# 02-USER_IO.net
KiCad netlist of a schematic drawn in Altium Designer
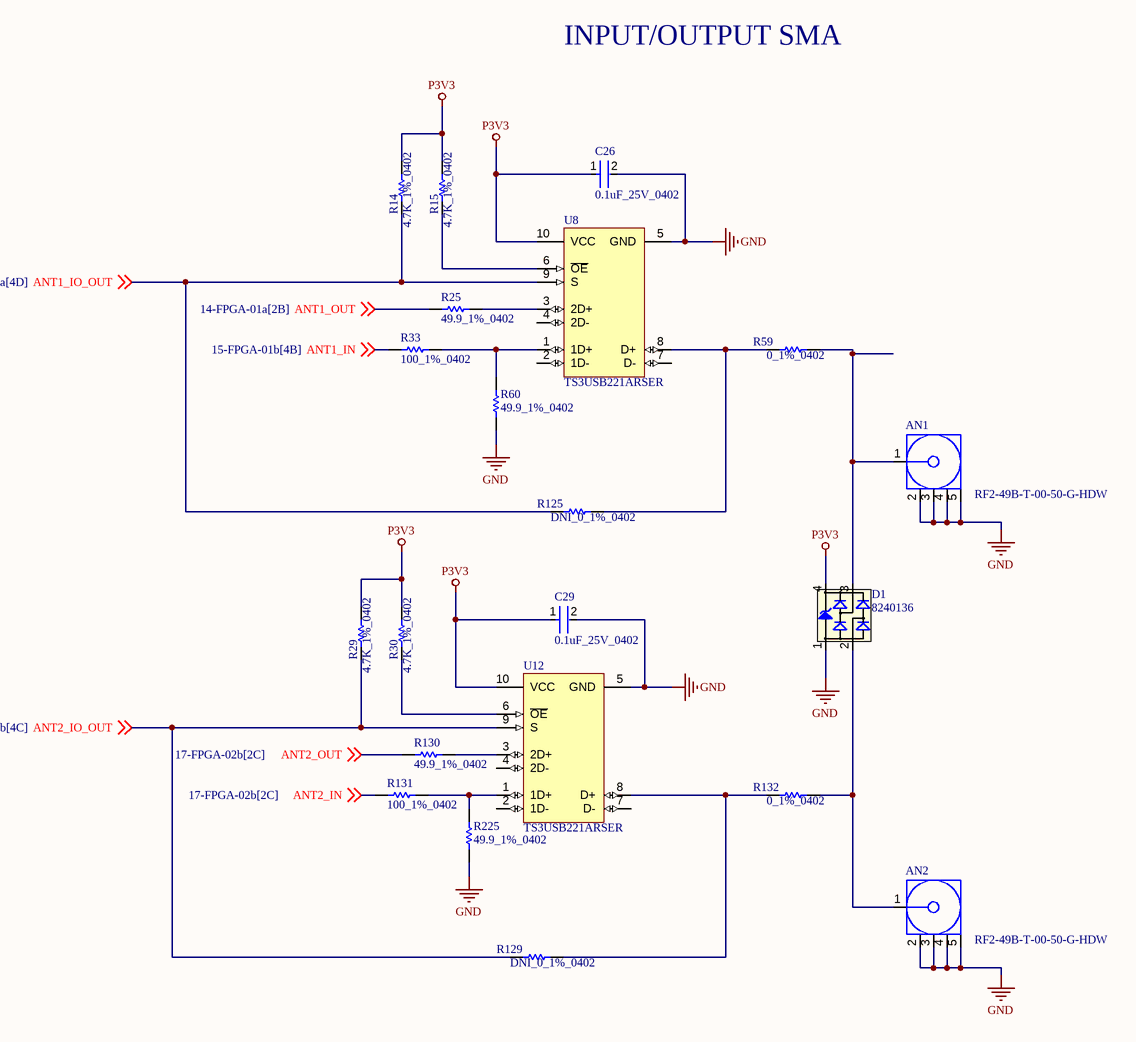
[diagram p0: 02-USER_IO.SchDoc]

(export (version "E")
  (design (tool "Eeschema 10.0.6"))
  (components
    (comp (ref "AN1")
      (value "RF2-49B-T-00-50-G-HDW")
      (footprint "AMPH-901-143-6RFX_V")
      (description "Coaxial connector, 50 Ohm, -65 to 165 degC, 5-Pin THD, RoHS, Bulk")
      (fields (field (name "MANUFACTURER") "Amphenol"))
      (libsource (lib "Altium Content Vault") (part "CN-S-4F-RF5"))
    )
    (comp (ref "AN2")
      (value "RF2-49B-T-00-50-G-HDW")
      (footprint "AMPH-901-143-6RFX_V")
      (description "Coaxial connector, 50 Ohm, -65 to 165 degC, 5-Pin THD, RoHS, Bulk")
      (fields (field (name "MANUFACTURER") "Amphenol"))
      (libsource (lib "Altium Content Vault") (part "CN-S-4F-RF5"))
    )
    (comp (ref "C26")
      (value "0.1uF_25V_0402")
      (footprint "FP-0402-L_1_0_1-W_0_5_0_1-IPC_C")
      (description "General Purpose Ceramic Capacitor, 0402, 100nF, 10%, X7R, 15%, 25V")
      (fields (field (name "VOLTAGE") "25V") (field (name "TOLERANCE") "10%"))
      (libsource (lib "Altium Content Vault") (part "b4654b650e69147ec39a6b967a45e02"))
    )
    (comp (ref "C29")
      (value "0.1uF_25V_0402")
      (footprint "FP-0402-L_1_0_1-W_0_5_0_1-IPC_C")
      (description "General Purpose Ceramic Capacitor, 0402, 100nF, 10%, X7R, 15%, 25V")
      (fields (field (name "VOLTAGE") "25V") (field (name "TOLERANCE") "10%"))
      (libsource (lib "Altium Content Vault") (part "b4654b650e69147ec39a6b967a45e02"))
    )
    (comp (ref "D1")
      (value "8240136")
      (footprint "SOT143-4L")
      (description "TVS Diode WE-TVS-HS, VRWM=3.3V")
      (fields (field (name "MANUFACTURER") "Wuerth Elektronik"))
      (libsource (lib "Altium Content Vault") (part "WE-TVS-HS-4"))
    )
    (comp (ref "R14")
      (value "4.7K_1%_0402")
      (footprint "RESC1005X40X25NL10T10")
      (fields (field (name "MANUFACTURER") "Bourns") (field (name "PART NUMBER") "CR0402-FX-4701GLF"))
      (libsource (lib "Altium Content Vault") (part "RES"))
    )
    (comp (ref "R15")
      (value "4.7K_1%_0402")
      (footprint "RESC1005X40X25NL10T10")
      (fields (field (name "MANUFACTURER") "Bourns") (field (name "PART NUMBER") "CR0402-FX-4701GLF"))
      (libsource (lib "Altium Content Vault") (part "RES"))
    )
    (comp (ref "R25")
      (value "49.9_1%_0402")
      (footprint "RESC1005X40X25NL10T10")
      (fields (field (name "PART NUMBER") "RK73H1ETTP49R9F") (field (name "MANUFACTURER") "KOA Speer"))
      (libsource (lib "Altium Content Vault") (part "RES"))
    )
    (comp (ref "R29")
      (value "4.7K_1%_0402")
      (footprint "RESC1005X40X25NL10T10")
      (fields (field (name "MANUFACTURER") "Bourns") (field (name "PART NUMBER") "CR0402-FX-4701GLF"))
      (libsource (lib "Altium Content Vault") (part "RES"))
    )
    (comp (ref "R30")
      (value "4.7K_1%_0402")
      (footprint "RESC1005X40X25NL10T10")
      (fields (field (name "MANUFACTURER") "Bourns") (field (name "PART NUMBER") "CR0402-FX-4701GLF"))
      (libsource (lib "Altium Content Vault") (part "RES"))
    )
    (comp (ref "R33")
      (value "100_1%_0402")
      (footprint "RESC1005X40X25NL05T10")
      (fields (field (name "MANUFACTURER") "Yageo") (field (name "PART NUMBER") "RC0402FR-13100RL"))
      (libsource (lib "Altium Content Vault") (part "RES"))
    )
    (comp (ref "R59")
      (value "0_1%_0402")
      (footprint "RESC1005X40X25LL05T05")
      (description "Chip Resistor, 0 Ohm, 0.1 W, -55 to 155 degC, 0402 (1005 Metric), RoHS, Tape and Reel")
      (fields (field (name "MANUFACTURER") "Panasonic") (field (name "TOLERANCE") "5%"))
      (libsource (lib "Altium Content Vault") (part "RES-2"))
    )
    (comp (ref "R60")
      (value "49.9_1%_0402")
      (footprint "RESC1005X40X25NL10T10")
      (fields (field (name "PART NUMBER") "RK73H1ETTP49R9F") (field (name "MANUFACTURER") "KOA Speer"))
      (libsource (lib "Altium Content Vault") (part "RES"))
    )
    (comp (ref "R125")
      (value "DNI_0_1%_0402")
      (footprint "RESC1005X40X25LL05T05")
      (description "Chip Resistor, 0 Ohm, 0.1 W, -55 to 155 degC, 0402 (1005 Metric), RoHS, Tape and Reel")
      (fields (field (name "MANUFACTURER") "Panasonic") (field (name "TOLERANCE") "5%"))
      (libsource (lib "Altium Content Vault") (part "RES-2"))
    )
    (comp (ref "R129")
      (value "DNI_0_1%_0402")
      (footprint "RESC1005X40X25LL05T05")
      (description "Chip Resistor, 0 Ohm, 0.1 W, -55 to 155 degC, 0402 (1005 Metric), RoHS, Tape and Reel")
      (fields (field (name "MANUFACTURER") "Panasonic") (field (name "TOLERANCE") "5%"))
      (libsource (lib "Altium Content Vault") (part "RES-2"))
    )
    (comp (ref "R130")
      (value "49.9_1%_0402")
      (footprint "RESC1005X40X25NL10T10")
      (fields (field (name "PART NUMBER") "RK73H1ETTP49R9F") (field (name "MANUFACTURER") "KOA Speer"))
      (libsource (lib "Altium Content Vault") (part "RES"))
    )
    (comp (ref "R131")
      (value "100_1%_0402")
      (footprint "RESC1005X40X25NL05T10")
      (fields (field (name "MANUFACTURER") "Yageo") (field (name "PART NUMBER") "RC0402FR-13100RL"))
      (libsource (lib "Altium Content Vault") (part "RES"))
    )
    (comp (ref "R132")
      (value "0_1%_0402")
      (footprint "RESC1005X40X25LL05T05")
      (description "Chip Resistor, 0 Ohm, 0.1 W, -55 to 155 degC, 0402 (1005 Metric), RoHS, Tape and Reel")
      (fields (field (name "MANUFACTURER") "Panasonic") (field (name "TOLERANCE") "5%"))
      (libsource (lib "Altium Content Vault") (part "RES-2"))
    )
    (comp (ref "R225")
      (value "49.9_1%_0402")
      (footprint "RESC1005X40X25NL10T10")
      (fields (field (name "PART NUMBER") "RK73H1ETTP49R9F") (field (name "MANUFACTURER") "KOA Speer"))
      (libsource (lib "Altium Content Vault") (part "RES"))
    )
    (comp (ref "U8")
      (value "TS3USB221ARSER")
      (footprint "RSE0010A_V")
      (fields (field (name "MANUFACTURER") "Texas Instruments"))
      (libsource (lib "Altium Content Vault") (part "TI-TS3USB221A-UQFN_RSE-10"))
    )
    (comp (ref "U12")
      (value "TS3USB221ARSER")
      (footprint "RSE0010A_V")
      (fields (field (name "MANUFACTURER") "Texas Instruments"))
      (libsource (lib "Altium Content Vault") (part "TI-TS3USB221A-UQFN_RSE-10"))
    )
  )
  (nets
    (net (code "1") (name "ANT1_IN") (class "Default")
      (node (ref "R33") (pin "1") (pinfunction "1_1") (pintype "passive"))
    )
    (net (code "2") (name "ANT1_IO_OUT") (class "Default")
      (node (ref "R125") (pin "1") (pinfunction "1_1") (pintype "passive"))
      (node (ref "R14") (pin "2") (pinfunction "2_2") (pintype "passive"))
      (node (ref "U8") (pin "9") (pinfunction "S_9") (pintype "input"))
    )
    (net (code "3") (name "ANT1_OUT") (class "Default")
      (node (ref "R25") (pin "1") (pinfunction "1_1") (pintype "passive"))
    )
    (net (code "4") (name "ANT2_IN") (class "Default")
      (node (ref "R131") (pin "1") (pinfunction "1_1") (pintype "passive"))
    )
    (net (code "5") (name "ANT2_IO_OUT") (class "Default")
      (node (ref "R129") (pin "1") (pinfunction "1_1") (pintype "passive"))
      (node (ref "R29") (pin "2") (pinfunction "2_2") (pintype "passive"))
      (node (ref "U12") (pin "9") (pinfunction "S_9") (pintype "input"))
    )
    (net (code "6") (name "ANT2_OUT") (class "Default")
      (node (ref "R130") (pin "1") (pinfunction "1_1") (pintype "passive"))
    )
    (net (code "7") (name "GND") (class "Default")
      (node (ref "AN1") (pin "2") (pinfunction "2_2") (pintype "passive"))
      (node (ref "AN1") (pin "3") (pinfunction "3_3") (pintype "passive"))
      (node (ref "AN1") (pin "4") (pinfunction "4_4") (pintype "passive"))
      (node (ref "AN1") (pin "5") (pinfunction "5_5") (pintype "passive"))
      (node (ref "AN2") (pin "2") (pinfunction "2_2") (pintype "passive"))
      (node (ref "AN2") (pin "3") (pinfunction "3_3") (pintype "passive"))
      (node (ref "AN2") (pin "4") (pinfunction "4_4") (pintype "passive"))
      (node (ref "AN2") (pin "5") (pinfunction "5_5") (pintype "passive"))
      (node (ref "C26") (pin "2") (pinfunction "2_2") (pintype "passive"))
      (node (ref "C29") (pin "2") (pinfunction "2_2") (pintype "passive"))
      (node (ref "D1") (pin "1") (pinfunction "GND_1") (pintype "passive"))
      (node (ref "R225") (pin "1") (pinfunction "1_1") (pintype "passive"))
      (node (ref "R60") (pin "1") (pinfunction "1_1") (pintype "passive"))
      (node (ref "U12") (pin "5") (pinfunction "GND_5") (pintype "power_in"))
      (node (ref "U8") (pin "5") (pinfunction "GND_5") (pintype "power_in"))
    )
    (net (code "8") (name "Net-(D1-I{slash}O1)") (class "Default")
      (node (ref "AN2") (pin "1") (pinfunction "1_1") (pintype "passive"))
      (node (ref "D1") (pin "2") (pinfunction "I/O1_2") (pintype "passive"))
      (node (ref "R132") (pin "2") (pinfunction "2_2") (pintype "passive"))
    )
    (net (code "9") (name "Net-(D1-I{slash}O2)") (class "Default")
      (node (ref "AN1") (pin "1") (pinfunction "1_1") (pintype "passive"))
      (node (ref "D1") (pin "3") (pinfunction "I/O2_3") (pintype "passive"))
      (node (ref "R59") (pin "2") (pinfunction "2_2") (pintype "passive"))
    )
    (net (code "10") (name "Net-(U8-1D+)") (class "Default")
      (node (ref "R33") (pin "2") (pinfunction "2_2") (pintype "passive"))
      (node (ref "R60") (pin "2") (pinfunction "2_2") (pintype "passive"))
      (node (ref "U8") (pin "1") (pinfunction "1D+_1") (pintype "bidirectional"))
    )
    (net (code "11") (name "Net-(U8-2D+)") (class "Default")
      (node (ref "R25") (pin "2") (pinfunction "2_2") (pintype "passive"))
      (node (ref "U8") (pin "3") (pinfunction "2D+_3") (pintype "bidirectional"))
    )
    (net (code "12") (name "Net-(U8-D+)") (class "Default")
      (node (ref "R125") (pin "2") (pinfunction "2_2") (pintype "passive"))
      (node (ref "R59") (pin "1") (pinfunction "1_1") (pintype "passive"))
      (node (ref "U8") (pin "8") (pinfunction "D+_8") (pintype "bidirectional"))
    )
    (net (code "13") (name "Net-(U8-~{OE})") (class "Default")
      (node (ref "R15") (pin "2") (pinfunction "2_2") (pintype "passive"))
      (node (ref "U8") (pin "6") (pinfunction "~{OE}_6") (pintype "input"))
    )
    (net (code "14") (name "Net-(U12-1D+)") (class "Default")
      (node (ref "R131") (pin "2") (pinfunction "2_2") (pintype "passive"))
      (node (ref "R225") (pin "2") (pinfunction "2_2") (pintype "passive"))
      (node (ref "U12") (pin "1") (pinfunction "1D+_1") (pintype "bidirectional"))
    )
    (net (code "15") (name "Net-(U12-2D+)") (class "Default")
      (node (ref "R130") (pin "2") (pinfunction "2_2") (pintype "passive"))
      (node (ref "U12") (pin "3") (pinfunction "2D+_3") (pintype "bidirectional"))
    )
    (net (code "16") (name "Net-(U12-D+)") (class "Default")
      (node (ref "R129") (pin "2") (pinfunction "2_2") (pintype "passive"))
      (node (ref "R132") (pin "1") (pinfunction "1_1") (pintype "passive"))
      (node (ref "U12") (pin "8") (pinfunction "D+_8") (pintype "bidirectional"))
    )
    (net (code "17") (name "Net-(U12-~{OE})") (class "Default")
      (node (ref "R30") (pin "2") (pinfunction "2_2") (pintype "passive"))
      (node (ref "U12") (pin "6") (pinfunction "~{OE}_6") (pintype "input"))
    )
    (net (code "18") (name "P3V3") (class "Default")
      (node (ref "C26") (pin "1") (pinfunction "1_1") (pintype "passive"))
      (node (ref "C29") (pin "1") (pinfunction "1_1") (pintype "passive"))
      (node (ref "D1") (pin "4") (pinfunction "VDD_4") (pintype "passive"))
      (node (ref "R14") (pin "1") (pinfunction "1_1") (pintype "passive"))
      (node (ref "R15") (pin "1") (pinfunction "1_1") (pintype "passive"))
      (node (ref "R29") (pin "1") (pinfunction "1_1") (pintype "passive"))
      (node (ref "R30") (pin "1") (pinfunction "1_1") (pintype "passive"))
      (node (ref "U12") (pin "10") (pinfunction "VCC_10") (pintype "power_in"))
      (node (ref "U8") (pin "10") (pinfunction "VCC_10") (pintype "power_in"))
    )
    (net (code "19") (name "unconnected-(U8-1D--Pad2)") (class "Default")
      (node (ref "U8") (pin "2") (pinfunction "1D-_2") (pintype "bidirectional"))
    )
    (net (code "20") (name "unconnected-(U8-2D--Pad4)") (class "Default")
      (node (ref "U8") (pin "4") (pinfunction "2D-_4") (pintype "bidirectional"))
    )
    (net (code "21") (name "unconnected-(U8-D--Pad7)") (class "Default")
      (node (ref "U8") (pin "7") (pinfunction "D-_7") (pintype "bidirectional"))
    )
    (net (code "22") (name "unconnected-(U12-1D--Pad2)") (class "Default")
      (node (ref "U12") (pin "2") (pinfunction "1D-_2") (pintype "bidirectional"))
    )
    (net (code "23") (name "unconnected-(U12-2D--Pad4)") (class "Default")
      (node (ref "U12") (pin "4") (pinfunction "2D-_4") (pintype "bidirectional"))
    )
    (net (code "24") (name "unconnected-(U12-D--Pad7)") (class "Default")
      (node (ref "U12") (pin "7") (pinfunction "D-_7") (pintype "bidirectional"))
    )
  )
)
